# mainboard.net
KiCad netlist of a schematic drawn in EAGLE
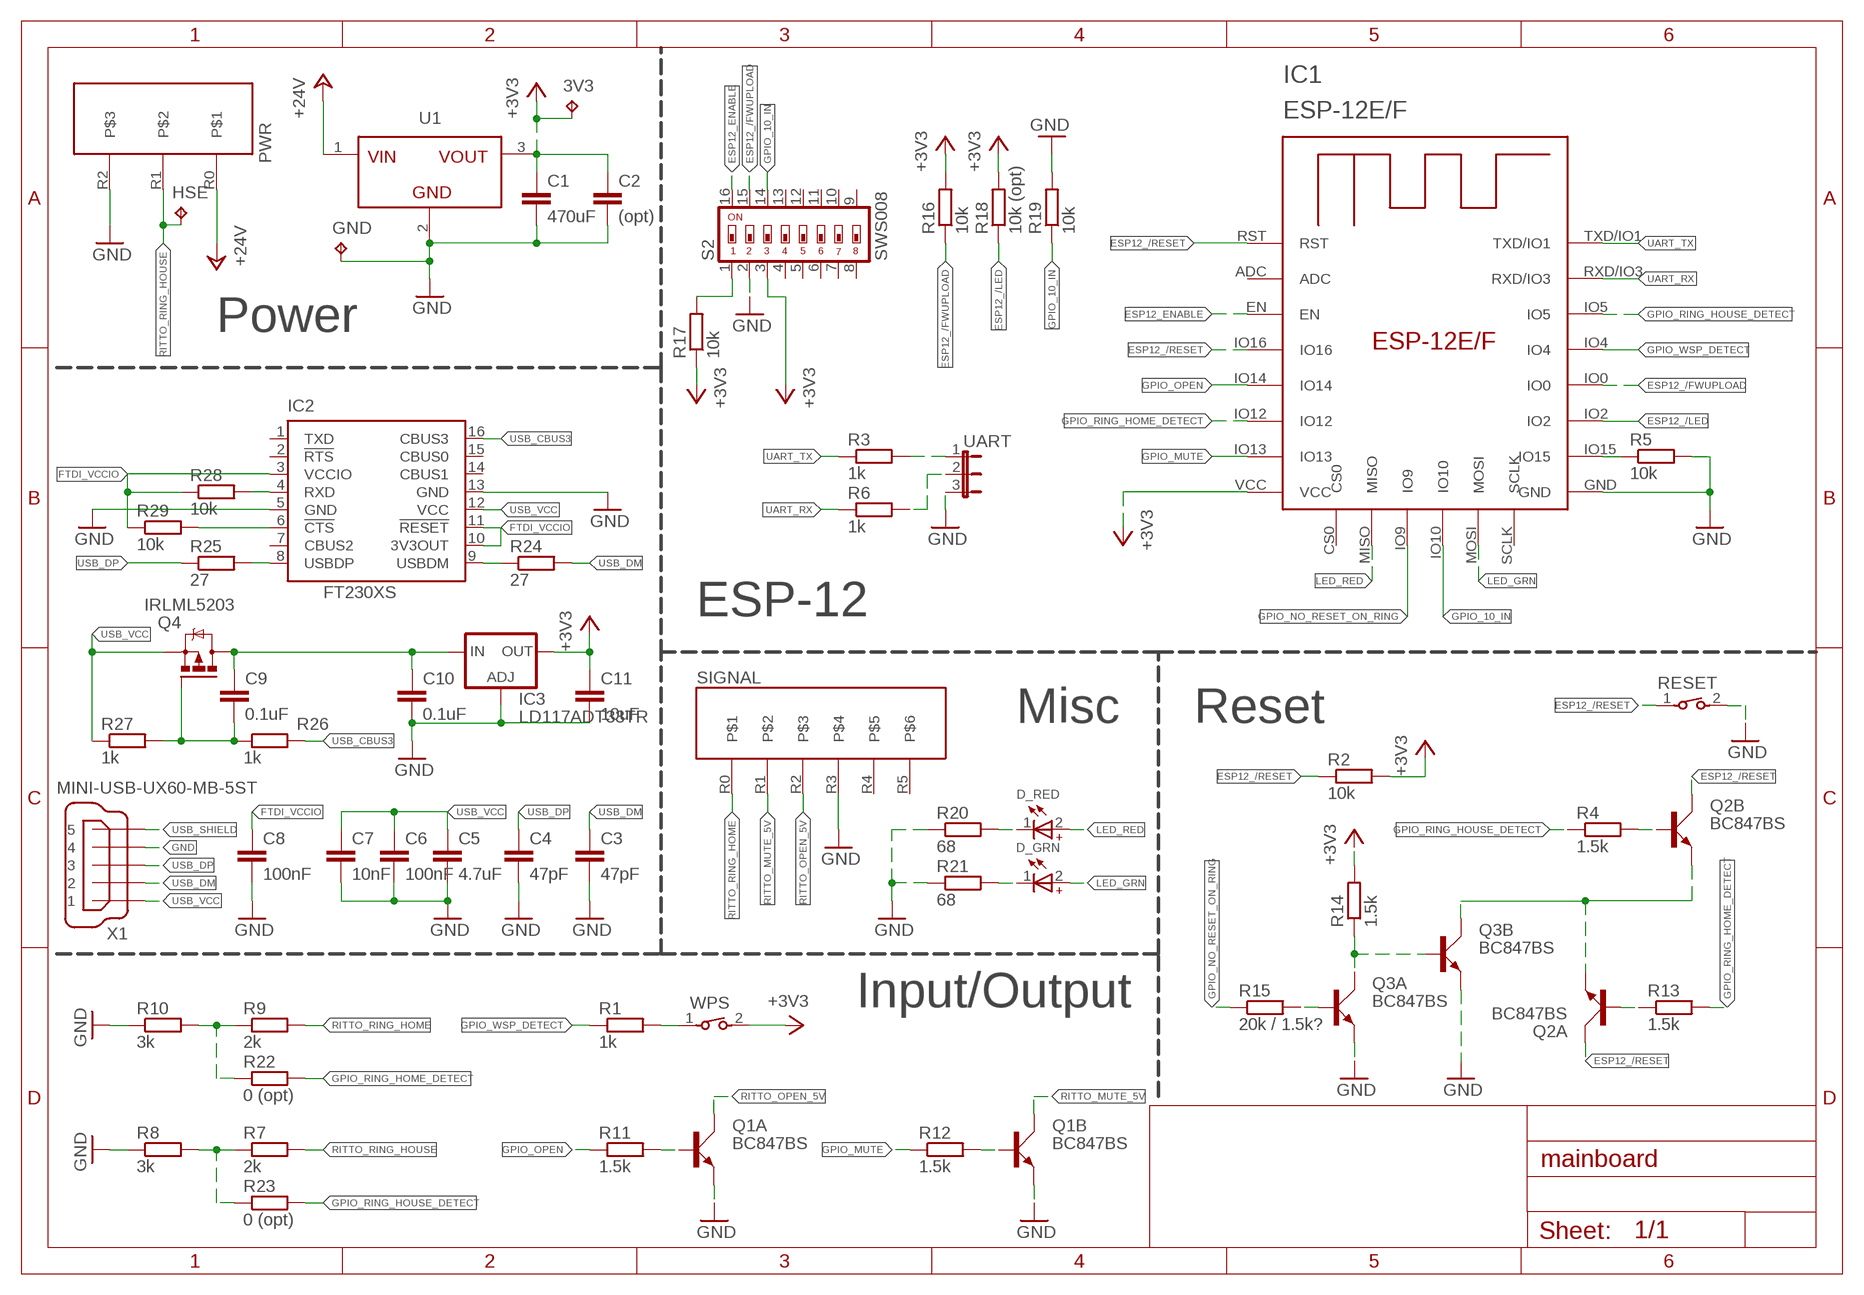
[diagram p0: schematic, sheet 1]

(export (version "E")
  (design (tool "Eeschema 10.0.6"))
  (components
    (comp (ref "3V3")
      (value "TPTP10SQ")
      (footprint "eagle-import:TP10SQ")
      (libsource (lib "eagle-import") (part "TPTP10SQ"))
    )
    (comp (ref "C1")
      (value "470uF")
      (footprint "eagle-import:C1206")
      (libsource (lib "eagle-import") (part "C-EUC1206"))
    )
    (comp (ref "C2")
      (value "(opt)")
      (footprint "eagle-import:C1206")
      (libsource (lib "eagle-import") (part "C-EUC1206"))
    )
    (comp (ref "C3")
      (value "47pF")
      (footprint "eagle-import:C1206")
      (libsource (lib "eagle-import") (part "C-EUC1206"))
    )
    (comp (ref "C4")
      (value "47pF")
      (footprint "eagle-import:C1206")
      (libsource (lib "eagle-import") (part "C-EUC1206"))
    )
    (comp (ref "C5")
      (value "4.7uF")
      (footprint "eagle-import:C1206")
      (libsource (lib "eagle-import") (part "C-EUC1206"))
    )
    (comp (ref "C6")
      (value "100nF")
      (footprint "eagle-import:C1206")
      (libsource (lib "eagle-import") (part "C-EUC1206"))
    )
    (comp (ref "C7")
      (value "10nF")
      (footprint "eagle-import:C1206")
      (libsource (lib "eagle-import") (part "C-EUC1206"))
    )
    (comp (ref "C8")
      (value "100nF")
      (footprint "eagle-import:C1206")
      (libsource (lib "eagle-import") (part "C-EUC1206"))
    )
    (comp (ref "C9")
      (value "0.1uF")
      (footprint "eagle-import:C1206")
      (libsource (lib "eagle-import") (part "C-EUC1206"))
    )
    (comp (ref "C10")
      (value "0.1uF")
      (footprint "eagle-import:C1206")
      (libsource (lib "eagle-import") (part "C-EUC1206"))
    )
    (comp (ref "C11")
      (value "10uF")
      (footprint "eagle-import:C1206")
      (libsource (lib "eagle-import") (part "C-EUC1206"))
    )
    (comp (ref "D_GRN")
      (value "WL-SMRW_1206_CYL_156120VS75300_NOR")
      (footprint "eagle-import:WL-SMRW_1206_CYL")
      (libsource (lib "eagle-import") (part "WL-SMRW_1206_CYL_NOR_156120VS75300"))
    )
    (comp (ref "D_RED")
      (value "WL-SMRW_1206_CYL_156120RS75300_NOR")
      (footprint "eagle-import:WL-SMRW_1206_CYL")
      (libsource (lib "eagle-import") (part "WL-SMRW_1206_CYL_NOR_156120RS75300"))
    )
    (comp (ref "GND")
      (value "TPTP10SQ")
      (footprint "eagle-import:TP10SQ")
      (libsource (lib "eagle-import") (part "TPTP10SQ"))
    )
    (comp (ref "HSE")
      (value "TPTP10SQ")
      (footprint "eagle-import:TP10SQ")
      (libsource (lib "eagle-import") (part "TPTP10SQ"))
    )
    (comp (ref "IC1")
      (value "ESP-12E/F")
      (footprint "eagle-import:ESP-12E")
      (libsource (lib "eagle-import") (part "ESP-12E/F"))
    )
    (comp (ref "IC2")
      (value "FT230XS")
      (footprint "eagle-import:SSOP16")
      (libsource (lib "eagle-import") (part "FT230XS"))
    )
    (comp (ref "IC3")
      (value "LD117ADT33TR")
      (footprint "eagle-import:DPACK")
      (libsource (lib "eagle-import") (part "LD117A?DT33TR"))
    )
    (comp (ref "PWR")
      (value "RAST_3")
      (footprint "eagle-import:RAST_3")
      (libsource (lib "eagle-import") (part "RAST_3"))
    )
    (comp (ref "Q1")
      (value "BC847BS")
      (footprint "eagle-import:SOT363_PHILIPS")
      (libsource (lib "eagle-import") (part "BC847BS"))
    )
    (comp (ref "Q2")
      (value "BC847BS")
      (footprint "eagle-import:SOT363_PHILIPS")
      (libsource (lib "eagle-import") (part "BC847BS"))
    )
    (comp (ref "Q3")
      (value "BC847BS")
      (footprint "eagle-import:SOT363_PHILIPS")
      (libsource (lib "eagle-import") (part "BC847BS"))
    )
    (comp (ref "Q4")
      (value "IRLML5203")
      (footprint "eagle-import:MICRO3")
      (libsource (lib "eagle-import") (part "IRLML5203"))
    )
    (comp (ref "R1")
      (value "1k")
      (footprint "eagle-import:R1206")
      (libsource (lib "eagle-import") (part "R-EU_R1206"))
    )
    (comp (ref "R2")
      (value "10k")
      (footprint "eagle-import:R1206")
      (libsource (lib "eagle-import") (part "R-EU_R1206"))
    )
    (comp (ref "R3")
      (value "1k")
      (footprint "eagle-import:R1206")
      (libsource (lib "eagle-import") (part "R-EU_R1206"))
    )
    (comp (ref "R4")
      (value "1.5k")
      (footprint "eagle-import:R1206")
      (libsource (lib "eagle-import") (part "R-EU_R1206"))
    )
    (comp (ref "R5")
      (value "10k")
      (footprint "eagle-import:R1206")
      (libsource (lib "eagle-import") (part "R-EU_R1206"))
    )
    (comp (ref "R6")
      (value "1k")
      (footprint "eagle-import:R1206")
      (libsource (lib "eagle-import") (part "R-EU_R1206"))
    )
    (comp (ref "R7")
      (value "2k")
      (footprint "eagle-import:R1206")
      (libsource (lib "eagle-import") (part "R-EU_R1206"))
    )
    (comp (ref "R8")
      (value "3k")
      (footprint "eagle-import:R1206")
      (libsource (lib "eagle-import") (part "R-EU_R1206"))
    )
    (comp (ref "R9")
      (value "2k")
      (footprint "eagle-import:R1206")
      (libsource (lib "eagle-import") (part "R-EU_R1206"))
    )
    (comp (ref "R10")
      (value "3k")
      (footprint "eagle-import:R1206")
      (libsource (lib "eagle-import") (part "R-EU_R1206"))
    )
    (comp (ref "R11")
      (value "1.5k")
      (footprint "eagle-import:R1206")
      (libsource (lib "eagle-import") (part "R-EU_R1206"))
    )
    (comp (ref "R12")
      (value "1.5k")
      (footprint "eagle-import:R1206")
      (libsource (lib "eagle-import") (part "R-EU_R1206"))
    )
    (comp (ref "R13")
      (value "1.5k")
      (footprint "eagle-import:R1206")
      (libsource (lib "eagle-import") (part "R-EU_R1206"))
    )
    (comp (ref "R14")
      (value "1.5k")
      (footprint "eagle-import:R1206")
      (libsource (lib "eagle-import") (part "R-EU_R1206"))
    )
    (comp (ref "R15")
      (value "20k / 1.5k?")
      (footprint "eagle-import:R1206")
      (libsource (lib "eagle-import") (part "R-EU_R1206"))
    )
    (comp (ref "R16")
      (value "10k")
      (footprint "eagle-import:R1206")
      (libsource (lib "eagle-import") (part "R-EU_R1206"))
    )
    (comp (ref "R17")
      (value "10k")
      (footprint "eagle-import:R1206")
      (libsource (lib "eagle-import") (part "R-EU_R1206"))
    )
    (comp (ref "R18")
      (value "10k (opt)")
      (footprint "eagle-import:R1206")
      (libsource (lib "eagle-import") (part "R-EU_R1206"))
    )
    (comp (ref "R19")
      (value "10k")
      (footprint "eagle-import:R1206")
      (libsource (lib "eagle-import") (part "R-EU_R1206"))
    )
    (comp (ref "R20")
      (value "68")
      (footprint "eagle-import:R1206")
      (libsource (lib "eagle-import") (part "R-EU_R1206"))
    )
    (comp (ref "R21")
      (value "68")
      (footprint "eagle-import:R1206")
      (libsource (lib "eagle-import") (part "R-EU_R1206"))
    )
    (comp (ref "R22")
      (value "0 (opt)")
      (footprint "eagle-import:R1206")
      (libsource (lib "eagle-import") (part "R-EU_R1206"))
    )
    (comp (ref "R23")
      (value "0 (opt)")
      (footprint "eagle-import:R1206")
      (libsource (lib "eagle-import") (part "R-EU_R1206"))
    )
    (comp (ref "R24")
      (value "27")
      (footprint "eagle-import:R1206")
      (libsource (lib "eagle-import") (part "R-EU_R1206"))
    )
    (comp (ref "R25")
      (value "27")
      (footprint "eagle-import:R1206")
      (libsource (lib "eagle-import") (part "R-EU_R1206"))
    )
    (comp (ref "R26")
      (value "1k")
      (footprint "eagle-import:R1206")
      (libsource (lib "eagle-import") (part "R-EU_R1206"))
    )
    (comp (ref "R27")
      (value "1k")
      (footprint "eagle-import:R1206")
      (libsource (lib "eagle-import") (part "R-EU_R1206"))
    )
    (comp (ref "R28")
      (value "10k")
      (footprint "eagle-import:R1206")
      (libsource (lib "eagle-import") (part "R-EU_R1206"))
    )
    (comp (ref "R29")
      (value "10k")
      (footprint "eagle-import:R1206")
      (libsource (lib "eagle-import") (part "R-EU_R1206"))
    )
    (comp (ref "RESET")
      (value "434123025816")
      (footprint "eagle-import:434123025816")
      (libsource (lib "eagle-import") (part "434123025816"))
    )
    (comp (ref "S2")
      (value "SWS008")
      (footprint "eagle-import:SMS-008")
      (libsource (lib "eagle-import") (part "SWS008"))
    )
    (comp (ref "SIGNAL")
      (value "RAST_6")
      (footprint "eagle-import:RAST_6")
      (libsource (lib "eagle-import") (part "RAST_6"))
    )
    (comp (ref "U1")
      (value "MAGI³C-FDSM_SIP-3_173950378_17395XX78")
      (footprint "eagle-import:MAGI³C-FDSM_17395XX78")
      (libsource (lib "eagle-import") (part "MAGI³C-FDSM_SIP-3_17395XX78_173950378"))
    )
    (comp (ref "UART")
      (value "JP2E")
      (footprint "eagle-import:JP2")
      (libsource (lib "eagle-import") (part "JP2E"))
    )
    (comp (ref "WPS")
      (value "434123025816")
      (footprint "eagle-import:434123025816")
      (libsource (lib "eagle-import") (part "434123025816"))
    )
    (comp (ref "X1")
      (value "MINI-USB-UX60-MB-5ST")
      (footprint "eagle-import:UX60-MB-5ST")
      (libsource (lib "eagle-import") (part "MINI-USB-UX60-MB-5ST"))
    )
  )
  (nets
    (net (code "1") (name "+3V3") (class "Default")
      (node (ref "3V3") (pin "TP") (pinfunction "TP_TP") (pintype "input"))
      (node (ref "C1") (pin "1") (pinfunction "1_1") (pintype "passive"))
      (node (ref "C11") (pin "1") (pinfunction "1_1") (pintype "passive"))
      (node (ref "C2") (pin "1") (pinfunction "1_1") (pintype "passive"))
      (node (ref "IC1") (pin "VCC") (pinfunction "VCC_VCC") (pintype "power_in"))
      (node (ref "IC3") (pin "4") (pinfunction "OUT_4") (pintype "passive"))
      (node (ref "R14") (pin "2") (pinfunction "2_2") (pintype "passive"))
      (node (ref "R16") (pin "2") (pinfunction "2_2") (pintype "passive"))
      (node (ref "R17") (pin "1") (pinfunction "1_1") (pintype "passive"))
      (node (ref "R18") (pin "2") (pinfunction "2_2") (pintype "passive"))
      (node (ref "R2") (pin "2") (pinfunction "2_2") (pintype "passive"))
      (node (ref "S2") (pin "3") (pinfunction "3_3") (pintype "passive"))
      (node (ref "U1") (pin "3") (pinfunction "VOUT_3") (pintype "output"))
      (node (ref "WPS") (pin "2") (pinfunction "2_2") (pintype "passive"))
    )
    (net (code "2") (name "+24V") (class "Default")
      (node (ref "PWR") (pin "R0") (pinfunction "P$1_R0") (pintype "passive"))
      (node (ref "U1") (pin "1") (pinfunction "VIN_1") (pintype "input"))
    )
    (net (code "3") (name "ESP12_ENABLE") (class "Default")
      (node (ref "IC1") (pin "EN") (pinfunction "EN_EN") (pintype "bidirectional"))
      (node (ref "S2") (pin "16") (pinfunction "16_16") (pintype "passive"))
    )
    (net (code "4") (name "ESP12_{slash}FWUPLOAD") (class "Default")
      (node (ref "IC1") (pin "IO0") (pinfunction "IO0_IO0") (pintype "bidirectional"))
      (node (ref "R16") (pin "1") (pinfunction "1_1") (pintype "passive"))
      (node (ref "S2") (pin "15") (pinfunction "15_15") (pintype "passive"))
    )
    (net (code "5") (name "ESP12_{slash}LED") (class "Default")
      (node (ref "IC1") (pin "IO2") (pinfunction "IO2_IO2") (pintype "bidirectional"))
      (node (ref "R18") (pin "1") (pinfunction "1_1") (pintype "passive"))
    )
    (net (code "6") (name "ESP12_{slash}RESET") (class "Default")
      (node (ref "IC1") (pin "IO16") (pinfunction "IO16_IO16") (pintype "bidirectional"))
      (node (ref "IC1") (pin "RST") (pinfunction "RST_RST") (pintype "input"))
      (node (ref "Q2") (pin "3") (pinfunction "C_3") (pintype "passive"))
      (node (ref "Q2") (pin "6") (pinfunction "C_6") (pintype "passive"))
      (node (ref "R2") (pin "1") (pinfunction "1_1") (pintype "passive"))
      (node (ref "RESET") (pin "1") (pinfunction "1_1") (pintype "passive"))
    )
    (net (code "7") (name "FTDI_VCCIO") (class "Default")
      (node (ref "C8") (pin "1") (pinfunction "1_1") (pintype "passive"))
      (node (ref "IC2") (pin "10") (pinfunction "3V3OUT_10") (pintype "output"))
      (node (ref "IC2") (pin "11") (pinfunction "~{RESET}_11") (pintype "input"))
      (node (ref "IC2") (pin "3") (pinfunction "VCCIO_3") (pintype "power_in"))
      (node (ref "R28") (pin "1") (pinfunction "1_1") (pintype "passive"))
      (node (ref "R29") (pin "1") (pinfunction "1_1") (pintype "passive"))
    )
    (net (code "8") (name "GND") (class "Default")
      (node (ref "C1") (pin "2") (pinfunction "2_2") (pintype "passive"))
      (node (ref "C10") (pin "2") (pinfunction "2_2") (pintype "passive"))
      (node (ref "C11") (pin "2") (pinfunction "2_2") (pintype "passive"))
      (node (ref "C2") (pin "2") (pinfunction "2_2") (pintype "passive"))
      (node (ref "C3") (pin "2") (pinfunction "2_2") (pintype "passive"))
      (node (ref "C4") (pin "2") (pinfunction "2_2") (pintype "passive"))
      (node (ref "C5") (pin "2") (pinfunction "2_2") (pintype "passive"))
      (node (ref "C6") (pin "2") (pinfunction "2_2") (pintype "passive"))
      (node (ref "C7") (pin "2") (pinfunction "2_2") (pintype "passive"))
      (node (ref "C8") (pin "2") (pinfunction "2_2") (pintype "passive"))
      (node (ref "GND") (pin "TP") (pinfunction "TP_TP") (pintype "input"))
      (node (ref "IC1") (pin "GND") (pinfunction "GND_GND") (pintype "power_in"))
      (node (ref "IC2") (pin "13") (pinfunction "GND_13") (pintype "power_in"))
      (node (ref "IC2") (pin "5") (pinfunction "GND_5") (pintype "power_in"))
      (node (ref "IC3") (pin "1") (pinfunction "ADJ_1") (pintype "input"))
      (node (ref "PWR") (pin "R2") (pinfunction "P$3_R2") (pintype "passive"))
      (node (ref "Q1") (pin "1") (pinfunction "E_1") (pintype "passive"))
      (node (ref "Q1") (pin "4") (pinfunction "E_4") (pintype "passive"))
      (node (ref "Q3") (pin "1") (pinfunction "E_1") (pintype "passive"))
      (node (ref "Q3") (pin "4") (pinfunction "E_4") (pintype "passive"))
      (node (ref "R10") (pin "1") (pinfunction "1_1") (pintype "passive"))
      (node (ref "R19") (pin "2") (pinfunction "2_2") (pintype "passive"))
      (node (ref "R20") (pin "1") (pinfunction "1_1") (pintype "passive"))
      (node (ref "R21") (pin "1") (pinfunction "1_1") (pintype "passive"))
      (node (ref "R5") (pin "2") (pinfunction "2_2") (pintype "passive"))
      (node (ref "R8") (pin "1") (pinfunction "1_1") (pintype "passive"))
      (node (ref "RESET") (pin "2") (pinfunction "2_2") (pintype "passive"))
      (node (ref "S2") (pin "2") (pinfunction "2_2") (pintype "passive"))
      (node (ref "SIGNAL") (pin "R3") (pinfunction "P$4_R3") (pintype "bidirectional"))
      (node (ref "U1") (pin "2") (pinfunction "GND_2") (pintype "passive"))
      (node (ref "UART") (pin "3") (pinfunction "3_3") (pintype "passive"))
      (node (ref "X1") (pin "4") (pinfunction "4_4") (pintype "input"))
    )
    (net (code "9") (name "GPIO_10_IN") (class "Default")
      (node (ref "IC1") (pin "IO10") (pinfunction "IO10_IO10") (pintype "bidirectional"))
      (node (ref "R19") (pin "1") (pinfunction "1_1") (pintype "passive"))
      (node (ref "S2") (pin "14") (pinfunction "14_14") (pintype "passive"))
    )
    (net (code "10") (name "GPIO_MUTE") (class "Default")
      (node (ref "IC1") (pin "IO13") (pinfunction "IO13_IO13") (pintype "bidirectional"))
      (node (ref "R12") (pin "1") (pinfunction "1_1") (pintype "passive"))
    )
    (net (code "11") (name "GPIO_NO_RESET_ON_RING") (class "Default")
      (node (ref "IC1") (pin "IO9") (pinfunction "IO9_IO9") (pintype "bidirectional"))
      (node (ref "R15") (pin "1") (pinfunction "1_1") (pintype "passive"))
    )
    (net (code "12") (name "GPIO_OPEN") (class "Default")
      (node (ref "IC1") (pin "IO14") (pinfunction "IO14_IO14") (pintype "bidirectional"))
      (node (ref "R11") (pin "1") (pinfunction "1_1") (pintype "passive"))
    )
    (net (code "13") (name "GPIO_RING_HOME_DETECT") (class "Default")
      (node (ref "IC1") (pin "IO12") (pinfunction "IO12_IO12") (pintype "bidirectional"))
      (node (ref "R13") (pin "2") (pinfunction "2_2") (pintype "passive"))
      (node (ref "R22") (pin "2") (pinfunction "2_2") (pintype "passive"))
    )
    (net (code "14") (name "GPIO_RING_HOUSE_DETECT") (class "Default")
      (node (ref "IC1") (pin "IO5") (pinfunction "IO5_IO5") (pintype "bidirectional"))
      (node (ref "R23") (pin "2") (pinfunction "2_2") (pintype "passive"))
      (node (ref "R4") (pin "1") (pinfunction "1_1") (pintype "passive"))
    )
    (net (code "15") (name "GPIO_WSP_DETECT") (class "Default")
      (node (ref "IC1") (pin "IO4") (pinfunction "IO4_IO4") (pintype "bidirectional"))
      (node (ref "R1") (pin "1") (pinfunction "1_1") (pintype "passive"))
    )
    (net (code "16") (name "LED_GRN") (class "Default")
      (node (ref "D_GRN") (pin "2") (pinfunction "+_2") (pintype "passive"))
      (node (ref "IC1") (pin "MOSI") (pinfunction "MOSI_MOSI") (pintype "bidirectional"))
    )
    (net (code "17") (name "LED_RED") (class "Default")
      (node (ref "D_RED") (pin "2") (pinfunction "+_2") (pintype "passive"))
      (node (ref "IC1") (pin "MISO") (pinfunction "MISO_MISO") (pintype "bidirectional"))
    )
    (net (code "18") (name "Net-(D_GRN--)") (class "Default")
      (node (ref "D_GRN") (pin "1") (pinfunction "-_1") (pintype "passive"))
      (node (ref "R21") (pin "2") (pinfunction "2_2") (pintype "passive"))
    )
    (net (code "19") (name "Net-(D_RED--)") (class "Default")
      (node (ref "D_RED") (pin "1") (pinfunction "-_1") (pintype "passive"))
      (node (ref "R20") (pin "2") (pinfunction "2_2") (pintype "passive"))
    )
    (net (code "20") (name "Net-(IC1-PadIO15)") (class "Default")
      (node (ref "IC1") (pin "IO15") (pinfunction "IO15_IO15") (pintype "bidirectional"))
      (node (ref "R5") (pin "1") (pinfunction "1_1") (pintype "passive"))
    )
    (net (code "21") (name "Net-(IC2-RXD)") (class "Default")
      (node (ref "IC2") (pin "4") (pinfunction "RXD_4") (pintype "input"))
      (node (ref "R28") (pin "2") (pinfunction "2_2") (pintype "passive"))
    )
    (net (code "22") (name "Net-(IC2-USBDM)") (class "Default")
      (node (ref "IC2") (pin "9") (pinfunction "USBDM_9") (pintype "input"))
      (node (ref "R24") (pin "1") (pinfunction "1_1") (pintype "passive"))
    )
    (net (code "23") (name "Net-(IC2-USBDP)") (class "Default")
      (node (ref "IC2") (pin "8") (pinfunction "USBDP_8") (pintype "input"))
      (node (ref "R25") (pin "2") (pinfunction "2_2") (pintype "passive"))
    )
    (net (code "24") (name "Net-(IC2-~{CTS})") (class "Default")
      (node (ref "IC2") (pin "6") (pinfunction "~{CTS}_6") (pintype "input"))
      (node (ref "R29") (pin "2") (pinfunction "2_2") (pintype "passive"))
    )
    (net (code "25") (name "Net-(IC3-IN)") (class "Default")
      (node (ref "C10") (pin "1") (pinfunction "1_1") (pintype "passive"))
      (node (ref "C9") (pin "1") (pinfunction "1_1") (pintype "passive"))
      (node (ref "IC3") (pin "3") (pinfunction "IN_3") (pintype "input"))
      (node (ref "Q4") (pin "3") (pinfunction "D_3") (pintype "passive"))
    )
    (net (code "26") (name "Net-(Q1A-B)") (class "Default")
      (node (ref "Q1") (pin "2") (pinfunction "B_2") (pintype "passive"))
      (node (ref "R11") (pin "2") (pinfunction "2_2") (pintype "passive"))
    )
    (net (code "27") (name "Net-(Q1B-B)") (class "Default")
      (node (ref "Q1") (pin "5") (pinfunction "B_5") (pintype "passive"))
      (node (ref "R12") (pin "2") (pinfunction "2_2") (pintype "passive"))
    )
    (net (code "28") (name "Net-(Q2A-B)") (class "Default")
      (node (ref "Q2") (pin "2") (pinfunction "B_2") (pintype "passive"))
      (node (ref "R13") (pin "1") (pinfunction "1_1") (pintype "passive"))
    )
    (net (code "29") (name "Net-(Q2A-E)") (class "Default")
      (node (ref "Q2") (pin "1") (pinfunction "E_1") (pintype "passive"))
      (node (ref "Q2") (pin "4") (pinfunction "E_4") (pintype "passive"))
      (node (ref "Q3") (pin "3") (pinfunction "C_3") (pintype "passive"))
    )
    (net (code "30") (name "Net-(Q2B-B)") (class "Default")
      (node (ref "Q2") (pin "5") (pinfunction "B_5") (pintype "passive"))
      (node (ref "R4") (pin "2") (pinfunction "2_2") (pintype "passive"))
    )
    (net (code "31") (name "Net-(Q3A-B)") (class "Default")
      (node (ref "Q3") (pin "2") (pinfunction "B_2") (pintype "passive"))
      (node (ref "R15") (pin "2") (pinfunction "2_2") (pintype "passive"))
    )
    (net (code "32") (name "Net-(Q3A-C)") (class "Default")
      (node (ref "Q3") (pin "5") (pinfunction "B_5") (pintype "passive"))
      (node (ref "Q3") (pin "6") (pinfunction "C_6") (pintype "passive"))
      (node (ref "R14") (pin "1") (pinfunction "1_1") (pintype "passive"))
    )
    (net (code "33") (name "Net-(Q4-G)") (class "Default")
      (node (ref "C9") (pin "2") (pinfunction "2_2") (pintype "passive"))
      (node (ref "Q4") (pin "1") (pinfunction "G_1") (pintype "passive"))
      (node (ref "R26") (pin "1") (pinfunction "1_1") (pintype "passive"))
      (node (ref "R27") (pin "2") (pinfunction "2_2") (pintype "passive"))
    )
    (net (code "34") (name "Net-(R1-Pad2)") (class "Default")
      (node (ref "R1") (pin "2") (pinfunction "2_2") (pintype "passive"))
      (node (ref "WPS") (pin "1") (pinfunction "1_1") (pintype "passive"))
    )
    (net (code "35") (name "Net-(R3-Pad2)") (class "Default")
      (node (ref "R3") (pin "2") (pinfunction "2_2") (pintype "passive"))
      (node (ref "UART") (pin "1") (pinfunction "1_1") (pintype "passive"))
    )
    (net (code "36") (name "Net-(R6-Pad2)") (class "Default")
      (node (ref "R6") (pin "2") (pinfunction "2_2") (pintype "passive"))
      (node (ref "UART") (pin "2") (pinfunction "2_2") (pintype "passive"))
    )
    (net (code "37") (name "Net-(R10-Pad2)") (class "Default")
      (node (ref "R10") (pin "2") (pinfunction "2_2") (pintype "passive"))
      (node (ref "R22") (pin "1") (pinfunction "1_1") (pintype "passive"))
      (node (ref "R9") (pin "1") (pinfunction "1_1") (pintype "passive"))
    )
    (net (code "38") (name "Net-(R17-Pad2)") (class "Default")
      (node (ref "R17") (pin "2") (pinfunction "2_2") (pintype "passive"))
      (node (ref "S2") (pin "1") (pinfunction "1_1") (pintype "passive"))
    )
    (net (code "39") (name "Net-(R23-Pad1)") (class "Default")
      (node (ref "R23") (pin "1") (pinfunction "1_1") (pintype "passive"))
      (node (ref "R7") (pin "1") (pinfunction "1_1") (pintype "passive"))
      (node (ref "R8") (pin "2") (pinfunction "2_2") (pintype "passive"))
    )
    (net (code "40") (name "RITTO_MUTE_5V") (class "Default")
      (node (ref "Q1") (pin "3") (pinfunction "C_3") (pintype "passive"))
      (node (ref "SIGNAL") (pin "R1") (pinfunction "P$2_R1") (pintype "bidirectional"))
    )
    (net (code "41") (name "RITTO_OPEN_5V") (class "Default")
      (node (ref "Q1") (pin "6") (pinfunction "C_6") (pintype "passive"))
      (node (ref "SIGNAL") (pin "R2") (pinfunction "P$3_R2") (pintype "bidirectional"))
    )
    (net (code "42") (name "RITTO_RING_HOME") (class "Default")
      (node (ref "R9") (pin "2") (pinfunction "2_2") (pintype "passive"))
      (node (ref "SIGNAL") (pin "R0") (pinfunction "P$1_R0") (pintype "bidirectional"))
    )
    (net (code "43") (name "RITTO_RING_HOUSE") (class "Default")
      (node (ref "HSE") (pin "TP") (pinfunction "TP_TP") (pintype "input"))
      (node (ref "PWR") (pin "R1") (pinfunction "P$2_R1") (pintype "passive"))
      (node (ref "R7") (pin "2") (pinfunction "2_2") (pintype "passive"))
    )
    (net (code "44") (name "UART_RX") (class "Default")
      (node (ref "IC1") (pin "RXD/IO3") (pinfunction "RXD/IO3_RXD/IO3") (pintype "bidirectional"))
      (node (ref "R6") (pin "1") (pinfunction "1_1") (pintype "passive"))
    )
    (net (code "45") (name "UART_TX") (class "Default")
      (node (ref "IC1") (pin "TXD/IO1") (pinfunction "TXD/IO1_TXD/IO1") (pintype "bidirectional"))
      (node (ref "R3") (pin "1") (pinfunction "1_1") (pintype "passive"))
    )
    (net (code "46") (name "USB_CBUS3") (class "Default")
      (node (ref "IC2") (pin "16") (pinfunction "CBUS3_16") (pintype "bidirectional"))
      (node (ref "R26") (pin "2") (pinfunction "2_2") (pintype "passive"))
    )
    (net (code "47") (name "USB_DM") (class "Default")
      (node (ref "C3") (pin "1") (pinfunction "1_1") (pintype "passive"))
      (node (ref "R24") (pin "2") (pinfunction "2_2") (pintype "passive"))
      (node (ref "X1") (pin "2") (pinfunction "2_2") (pintype "input"))
    )
    (net (code "48") (name "USB_DP") (class "Default")
      (node (ref "C4") (pin "1") (pinfunction "1_1") (pintype "passive"))
      (node (ref "R25") (pin "1") (pinfunction "1_1") (pintype "passive"))
      (node (ref "X1") (pin "3") (pinfunction "3_3") (pintype "input"))
    )
    (net (code "49") (name "USB_SHIELD") (class "Default")
      (node (ref "X1") (pin "5") (pinfunction "5_5") (pintype "input"))
    )
    (net (code "50") (name "USB_VCC") (class "Default")
      (node (ref "C5") (pin "1") (pinfunction "1_1") (pintype "passive"))
      (node (ref "C6") (pin "1") (pinfunction "1_1") (pintype "passive"))
      (node (ref "C7") (pin "1") (pinfunction "1_1") (pintype "passive"))
      (node (ref "IC2") (pin "12") (pinfunction "VCC_12") (pintype "power_in"))
      (node (ref "Q4") (pin "2") (pinfunction "S_2") (pintype "passive"))
      (node (ref "R27") (pin "1") (pinfunction "1_1") (pintype "passive"))
      (node (ref "X1") (pin "1") (pinfunction "1_1") (pintype "input"))
    )
    (net (code "51") (name "unconnected-(IC1-PadADC)") (class "Default")
      (node (ref "IC1") (pin "ADC") (pinfunction "ADC_ADC") (pintype "bidirectional"))
    )
    (net (code "52") (name "unconnected-(IC1-PadCS0)") (class "Default")
      (node (ref "IC1") (pin "CS0") (pinfunction "CS0_CS0") (pintype "bidirectional"))
    )
    (net (code "53") (name "unconnected-(IC1-PadSCLK)") (class "Default")
      (node (ref "IC1") (pin "SCLK") (pinfunction "SCLK_SCLK") (pintype "bidirectional"))
    )
    (net (code "54") (name "unconnected-(IC2-CBUS0-Pad15)") (class "Default")
      (node (ref "IC2") (pin "15") (pinfunction "CBUS0_15") (pintype "bidirectional"))
    )
    (net (code "55") (name "unconnected-(IC2-CBUS1-Pad14)") (class "Default")
      (node (ref "IC2") (pin "14") (pinfunction "CBUS1_14") (pintype "bidirectional"))
    )
    (net (code "56") (name "unconnected-(IC2-CBUS2-Pad7)") (class "Default")
      (node (ref "IC2") (pin "7") (pinfunction "CBUS2_7") (pintype "bidirectional"))
    )
    (net (code "57") (name "unconnected-(IC2-TXD-Pad1)") (class "Default")
      (node (ref "IC2") (pin "1") (pinfunction "TXD_1") (pintype "output"))
    )
    (net (code "58") (name "unconnected-(IC2-~{RTS}-Pad2)") (class "Default")
      (node (ref "IC2") (pin "2") (pinfunction "~{RTS}_2") (pintype "output"))
    )
    (net (code "59") (name "unconnected-(S2-Pad4)") (class "Default")
      (node (ref "S2") (pin "4") (pinfunction "4_4") (pintype "passive"))
    )
    (net (code "60") (name "unconnected-(S2-Pad5)") (class "Default")
      (node (ref "S2") (pin "5") (pinfunction "5_5") (pintype "passive"))
    )
    (net (code "61") (name "unconnected-(S2-Pad6)") (class "Default")
      (node (ref "S2") (pin "6") (pinfunction "6_6") (pintype "passive"))
    )
    (net (code "62") (name "unconnected-(S2-Pad7)") (class "Default")
      (node (ref "S2") (pin "7") (pinfunction "7_7") (pintype "passive"))
    )
    (net (code "63") (name "unconnected-(S2-Pad8)") (class "Default")
      (node (ref "S2") (pin "8") (pinfunction "8_8") (pintype "passive"))
    )
    (net (code "64") (name "unconnected-(S2-Pad9)") (class "Default")
      (node (ref "S2") (pin "9") (pinfunction "9_9") (pintype "passive"))
    )
    (net (code "65") (name "unconnected-(S2-Pad10)") (class "Default")
      (node (ref "S2") (pin "10") (pinfunction "10_10") (pintype "passive"))
    )
    (net (code "66") (name "unconnected-(S2-Pad11)") (class "Default")
      (node (ref "S2") (pin "11") (pinfunction "11_11") (pintype "passive"))
    )
    (net (code "67") (name "unconnected-(S2-Pad12)") (class "Default")
      (node (ref "S2") (pin "12") (pinfunction "12_12") (pintype "passive"))
    )
    (net (code "68") (name "unconnected-(S2-Pad13)") (class "Default")
      (node (ref "S2") (pin "13") (pinfunction "13_13") (pintype "passive"))
    )
    (net (code "69") (name "unconnected-(SIGNAL-P$5-PadR4)") (class "Default")
      (node (ref "SIGNAL") (pin "R4") (pinfunction "P$5_R4") (pintype "bidirectional"))
    )
    (net (code "70") (name "unconnected-(SIGNAL-P$6-PadR5)") (class "Default")
      (node (ref "SIGNAL") (pin "R5") (pinfunction "P$6_R5") (pintype "bidirectional"))
    )
  )
)
